# Debug_Breakout.net
KiCad netlist of a schematic drawn in EAGLE
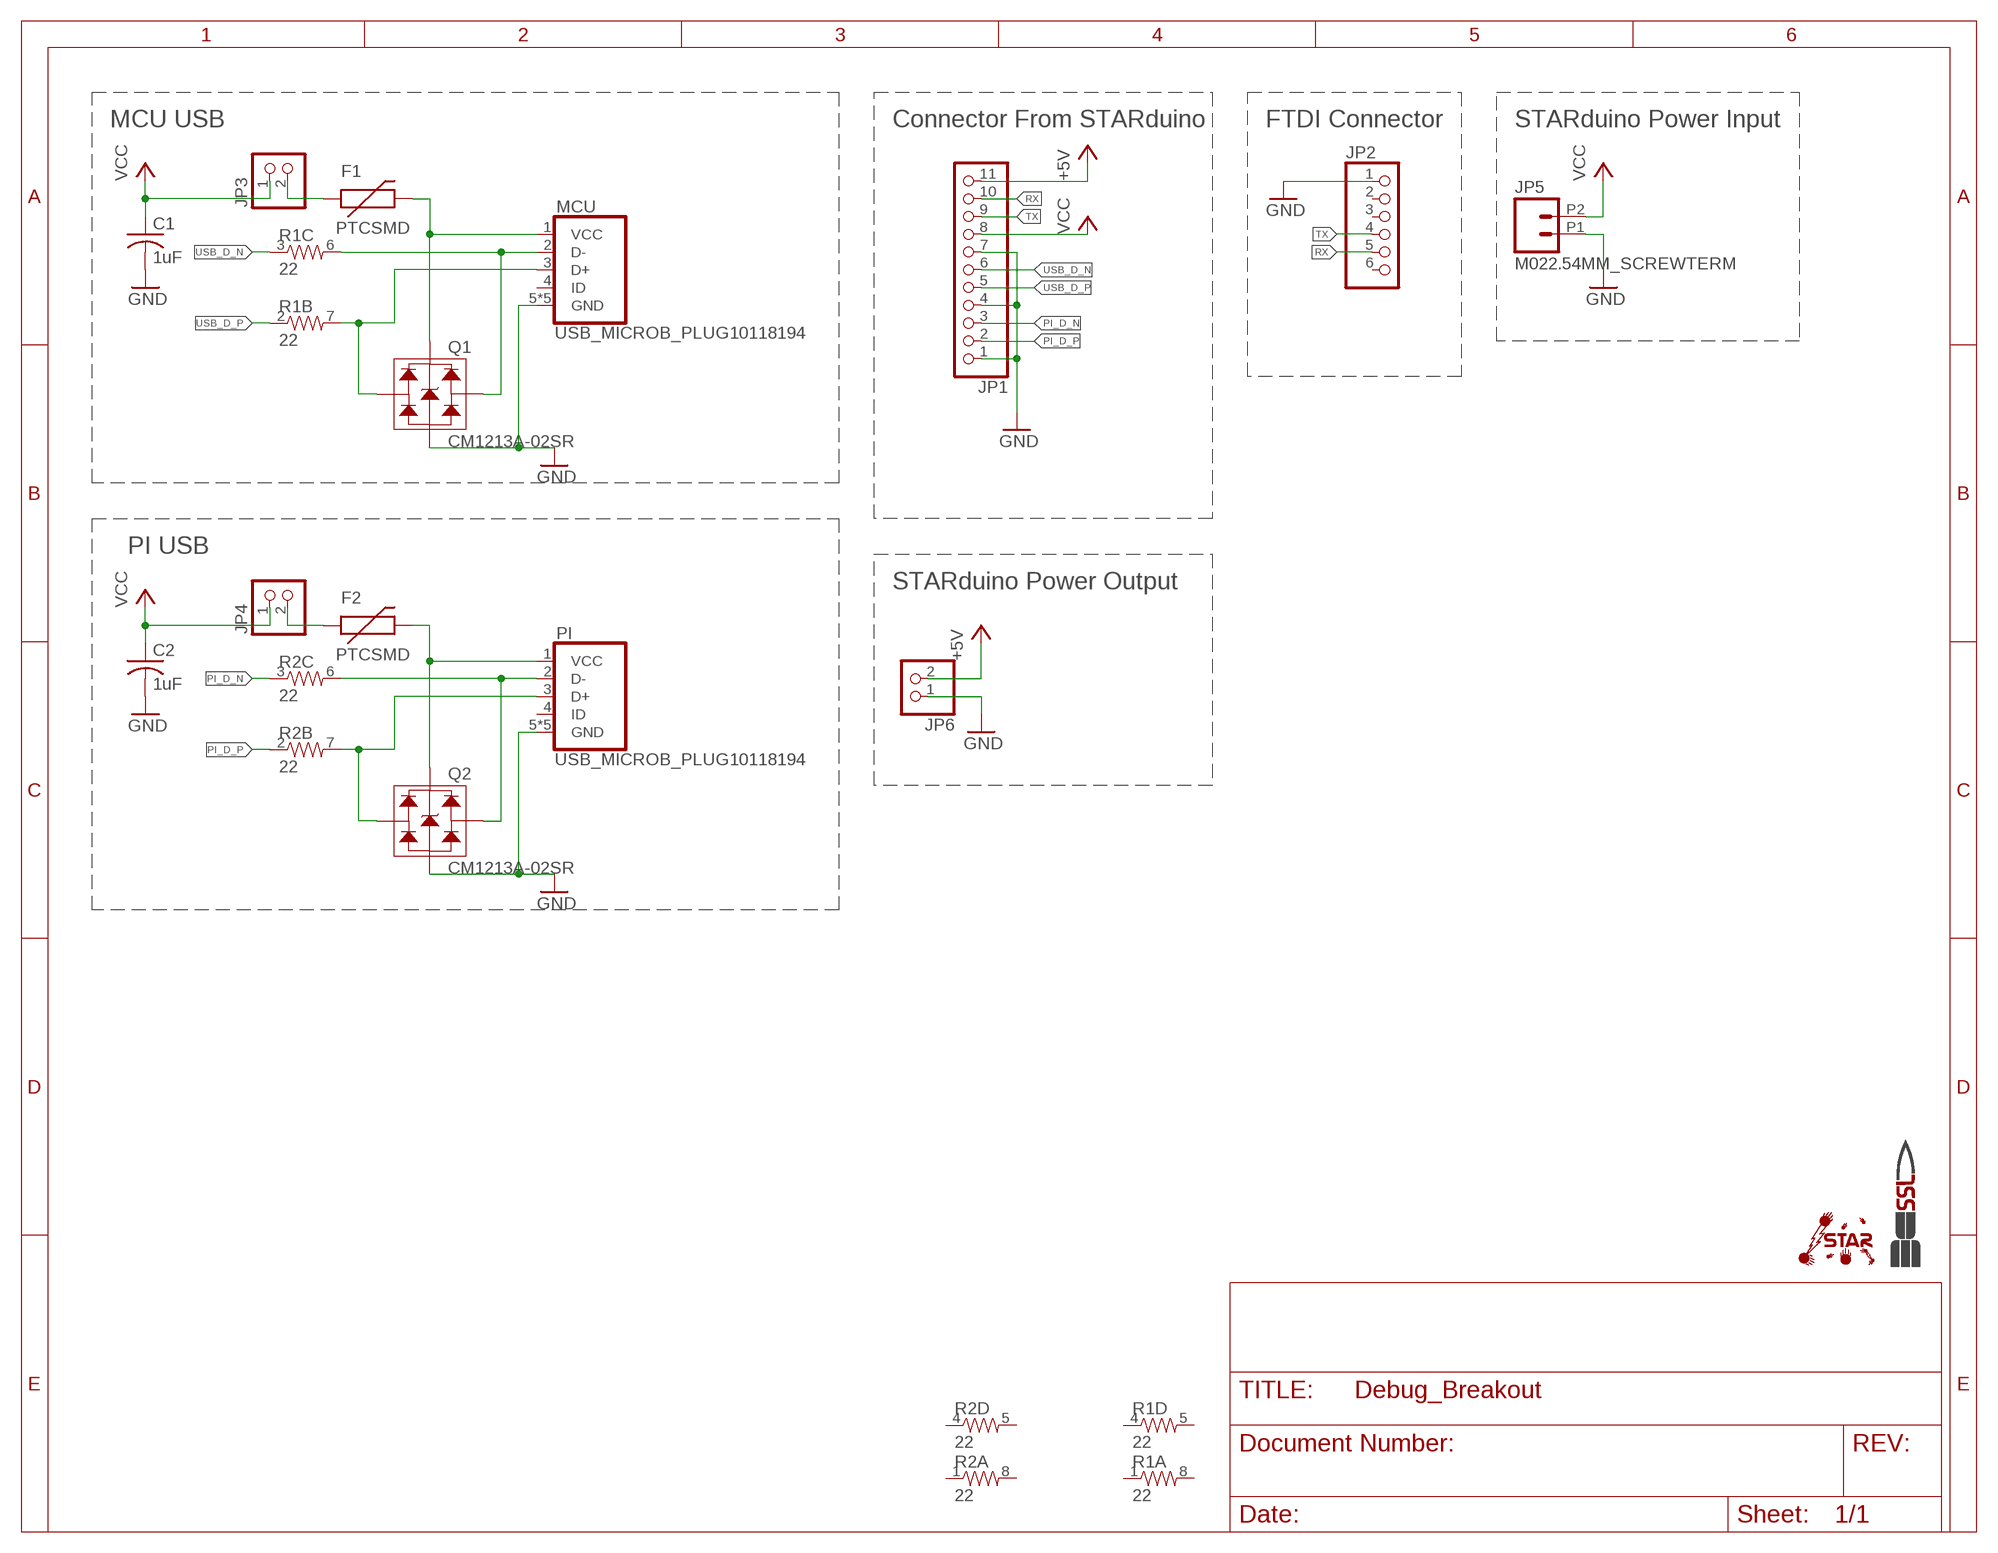
[diagram p0: schematic, sheet 1]

(export (version "E")
  (design (tool "Eeschema 10.0.6"))
  (components
    (comp (ref "C1")
      (value "1uF")
      (footprint "eagle-import:C0603")
      (libsource (lib "eagle-import") (part "C-USC0603"))
    )
    (comp (ref "C2")
      (value "1uF")
      (footprint "eagle-import:C0603")
      (libsource (lib "eagle-import") (part "C-USC0603"))
    )
    (comp (ref "F1")
      (value "PTCSMD")
      (footprint "eagle-import:PTC-1206")
      (libsource (lib "eagle-import") (part "PTCSMD"))
    )
    (comp (ref "F2")
      (value "PTCSMD")
      (footprint "eagle-import:PTC-1206")
      (libsource (lib "eagle-import") (part "PTCSMD"))
    )
    (comp (ref "JP1")
      (value "PINHD-1X11")
      (footprint "eagle-import:1X11")
      (libsource (lib "eagle-import") (part "PINHD-1X11"))
    )
    (comp (ref "JP2")
      (value "PINHD-1X6")
      (footprint "eagle-import:1X06")
      (libsource (lib "eagle-import") (part "PINHD-1X6"))
    )
    (comp (ref "JP3")
      (value "PINHD-1X2")
      (footprint "eagle-import:1X02")
      (libsource (lib "eagle-import") (part "PINHD-1X2"))
    )
    (comp (ref "JP4")
      (value "PINHD-1X2")
      (footprint "eagle-import:1X02")
      (libsource (lib "eagle-import") (part "PINHD-1X2"))
    )
    (comp (ref "JP5")
      (value "M022.54MM_SCREWTERM")
      (footprint "eagle-import:1X02_2.54_SCREWTERM")
      (libsource (lib "eagle-import") (part "M022.54MM_SCREWTERM"))
    )
    (comp (ref "JP6")
      (value "PINHD-1X2")
      (footprint "eagle-import:1X02")
      (libsource (lib "eagle-import") (part "PINHD-1X2"))
    )
    (comp (ref "MCU")
      (value "USB_MICROB_PLUG10118194")
      (footprint "eagle-import:MICRO-B-10118194")
      (libsource (lib "eagle-import") (part "USB_MICROB_PLUG10118194"))
    )
    (comp (ref "PI")
      (value "USB_MICROB_PLUG10118194")
      (footprint "eagle-import:MICRO-B-10118194")
      (libsource (lib "eagle-import") (part "USB_MICROB_PLUG10118194"))
    )
    (comp (ref "Q1")
      (value "CM1213A-02SR")
      (footprint "eagle-import:SOT143-4")
      (libsource (lib "eagle-import") (part "CM1213A-02SR"))
    )
    (comp (ref "Q2")
      (value "CM1213A-02SR")
      (footprint "eagle-import:SOT143-4")
      (libsource (lib "eagle-import") (part "CM1213A-02SR"))
    )
    (comp (ref "R1")
      (value "22")
      (footprint "eagle-import:0603-ARV")
      (libsource (lib "eagle-import") (part "RESISTOR-ARRAY0603-ARV"))
    )
    (comp (ref "R2")
      (value "22")
      (footprint "eagle-import:0603-ARV")
      (libsource (lib "eagle-import") (part "RESISTOR-ARRAY0603-ARV"))
    )
    (comp (ref "U$1")
      (value "SSL.3IN_SILK")
      (footprint "eagle-import:SSL_SILK_.3IN")
      (libsource (lib "eagle-import") (part "SSL.3IN_SILK"))
    )
    (comp (ref "U$2")
      (value "STAR")
      (footprint "eagle-import:STAR_.3IN")
      (libsource (lib "eagle-import") (part "STAR"))
    )
  )
  (nets
    (net (code "1") (name "+5V") (class "Default")
      (node (ref "JP1") (pin "11") (pinfunction "11_11") (pintype "passive"))
      (node (ref "JP6") (pin "2") (pinfunction "2_2") (pintype "passive"))
    )
    (net (code "2") (name "GND") (class "Default")
      (node (ref "C1") (pin "2") (pinfunction "2_2") (pintype "passive"))
      (node (ref "C2") (pin "2") (pinfunction "2_2") (pintype "passive"))
      (node (ref "JP1") (pin "1") (pinfunction "1_1") (pintype "passive"))
      (node (ref "JP1") (pin "4") (pinfunction "4_4") (pintype "passive"))
      (node (ref "JP1") (pin "7") (pinfunction "7_7") (pintype "passive"))
      (node (ref "JP2") (pin "1") (pinfunction "1_1") (pintype "passive"))
      (node (ref "JP5") (pin "P1") (pinfunction "1_P1") (pintype "passive"))
      (node (ref "JP6") (pin "1") (pinfunction "1_1") (pintype "passive"))
      (node (ref "MCU") (pin "5") (pinfunction "GND_5") (pintype "bidirectional"))
      (node (ref "MCU") (pin "S1") (pinfunction "GND_S1") (pintype "bidirectional"))
      (node (ref "MCU") (pin "S2") (pinfunction "GND_S2") (pintype "bidirectional"))
      (node (ref "MCU") (pin "S3") (pinfunction "GND_S3") (pintype "bidirectional"))
      (node (ref "MCU") (pin "S4") (pinfunction "GND_S4") (pintype "bidirectional"))
      (node (ref "PI") (pin "5") (pinfunction "GND_5") (pintype "bidirectional"))
      (node (ref "PI") (pin "S1") (pinfunction "GND_S1") (pintype "bidirectional"))
      (node (ref "PI") (pin "S2") (pinfunction "GND_S2") (pintype "bidirectional"))
      (node (ref "PI") (pin "S3") (pinfunction "GND_S3") (pintype "bidirectional"))
      (node (ref "PI") (pin "S4") (pinfunction "GND_S4") (pintype "bidirectional"))
      (node (ref "Q1") (pin "P$1") (pinfunction "GND_P$1") (pintype "bidirectional"))
      (node (ref "Q2") (pin "P$1") (pinfunction "GND_P$1") (pintype "bidirectional"))
    )
    (net (code "3") (name "Net-(F1-Pad1)") (class "Default")
      (node (ref "F1") (pin "1") (pinfunction "1_1") (pintype "bidirectional"))
      (node (ref "JP3") (pin "2") (pinfunction "2_2") (pintype "passive"))
    )
    (net (code "4") (name "Net-(F2-Pad1)") (class "Default")
      (node (ref "F2") (pin "1") (pinfunction "1_1") (pintype "bidirectional"))
      (node (ref "JP4") (pin "2") (pinfunction "2_2") (pintype "passive"))
    )
    (net (code "5") (name "Net-(MCU-D+)") (class "Default")
      (node (ref "MCU") (pin "3") (pinfunction "D+_3") (pintype "bidirectional"))
      (node (ref "Q1") (pin "P$2") (pinfunction "CH1_P$2") (pintype "bidirectional"))
      (node (ref "R1") (pin "7") (pinfunction "2_7") (pintype "passive"))
    )
    (net (code "6") (name "Net-(MCU-D-)") (class "Default")
      (node (ref "MCU") (pin "2") (pinfunction "D-_2") (pintype "bidirectional"))
      (node (ref "Q1") (pin "P$3") (pinfunction "CH2_P$3") (pintype "bidirectional"))
      (node (ref "R1") (pin "6") (pinfunction "2_6") (pintype "passive"))
    )
    (net (code "7") (name "Net-(MCU-VCC)") (class "Default")
      (node (ref "F1") (pin "2") (pinfunction "2_2") (pintype "bidirectional"))
      (node (ref "MCU") (pin "1") (pinfunction "VCC_1") (pintype "bidirectional"))
      (node (ref "Q1") (pin "P$4") (pinfunction "VCC_P$4") (pintype "bidirectional"))
    )
    (net (code "8") (name "Net-(PI-D+)") (class "Default")
      (node (ref "PI") (pin "3") (pinfunction "D+_3") (pintype "bidirectional"))
      (node (ref "Q2") (pin "P$2") (pinfunction "CH1_P$2") (pintype "bidirectional"))
      (node (ref "R2") (pin "7") (pinfunction "2_7") (pintype "passive"))
    )
    (net (code "9") (name "Net-(PI-D-)") (class "Default")
      (node (ref "PI") (pin "2") (pinfunction "D-_2") (pintype "bidirectional"))
      (node (ref "Q2") (pin "P$3") (pinfunction "CH2_P$3") (pintype "bidirectional"))
      (node (ref "R2") (pin "6") (pinfunction "2_6") (pintype "passive"))
    )
    (net (code "10") (name "Net-(PI-VCC)") (class "Default")
      (node (ref "F2") (pin "2") (pinfunction "2_2") (pintype "bidirectional"))
      (node (ref "PI") (pin "1") (pinfunction "VCC_1") (pintype "bidirectional"))
      (node (ref "Q2") (pin "P$4") (pinfunction "VCC_P$4") (pintype "bidirectional"))
    )
    (net (code "11") (name "PI_D_N") (class "Default")
      (node (ref "JP1") (pin "3") (pinfunction "3_3") (pintype "passive"))
      (node (ref "R2") (pin "3") (pinfunction "1_3") (pintype "passive"))
    )
    (net (code "12") (name "PI_D_P") (class "Default")
      (node (ref "JP1") (pin "2") (pinfunction "2_2") (pintype "passive"))
      (node (ref "R2") (pin "2") (pinfunction "1_2") (pintype "passive"))
    )
    (net (code "13") (name "RX") (class "Default")
      (node (ref "JP1") (pin "10") (pinfunction "10_10") (pintype "passive"))
      (node (ref "JP2") (pin "5") (pinfunction "5_5") (pintype "passive"))
    )
    (net (code "14") (name "TX") (class "Default")
      (node (ref "JP1") (pin "9") (pinfunction "9_9") (pintype "passive"))
      (node (ref "JP2") (pin "4") (pinfunction "4_4") (pintype "passive"))
    )
    (net (code "15") (name "USB_D_N") (class "Default")
      (node (ref "JP1") (pin "6") (pinfunction "6_6") (pintype "passive"))
      (node (ref "R1") (pin "3") (pinfunction "1_3") (pintype "passive"))
    )
    (net (code "16") (name "USB_D_P") (class "Default")
      (node (ref "JP1") (pin "5") (pinfunction "5_5") (pintype "passive"))
      (node (ref "R1") (pin "2") (pinfunction "1_2") (pintype "passive"))
    )
    (net (code "17") (name "VCC") (class "Default")
      (node (ref "C1") (pin "1") (pinfunction "1_1") (pintype "passive"))
      (node (ref "C2") (pin "1") (pinfunction "1_1") (pintype "passive"))
      (node (ref "JP1") (pin "8") (pinfunction "8_8") (pintype "passive"))
      (node (ref "JP3") (pin "1") (pinfunction "1_1") (pintype "passive"))
      (node (ref "JP4") (pin "1") (pinfunction "1_1") (pintype "passive"))
      (node (ref "JP5") (pin "P2") (pinfunction "2_P2") (pintype "passive"))
    )
    (net (code "18") (name "unconnected-(JP2-Pad2)") (class "Default")
      (node (ref "JP2") (pin "2") (pinfunction "2_2") (pintype "passive"))
    )
    (net (code "19") (name "unconnected-(JP2-Pad3)") (class "Default")
      (node (ref "JP2") (pin "3") (pinfunction "3_3") (pintype "passive"))
    )
    (net (code "20") (name "unconnected-(JP2-Pad6)") (class "Default")
      (node (ref "JP2") (pin "6") (pinfunction "6_6") (pintype "passive"))
    )
    (net (code "21") (name "unconnected-(MCU-ID-Pad4)") (class "Default")
      (node (ref "MCU") (pin "4") (pinfunction "ID_4") (pintype "bidirectional"))
    )
    (net (code "22") (name "unconnected-(PI-ID-Pad4)") (class "Default")
      (node (ref "PI") (pin "4") (pinfunction "ID_4") (pintype "bidirectional"))
    )
    (net (code "23") (name "unconnected-(R1-Pad1)") (class "Default")
      (node (ref "R1") (pin "1") (pinfunction "1_1") (pintype "passive"))
    )
    (net (code "24") (name "unconnected-(R1A-2-Pad8)") (class "Default")
      (node (ref "R1") (pin "8") (pinfunction "2_8") (pintype "passive"))
    )
    (net (code "25") (name "unconnected-(R1D-1-Pad4)") (class "Default")
      (node (ref "R1") (pin "4") (pinfunction "1_4") (pintype "passive"))
    )
    (net (code "26") (name "unconnected-(R1D-2-Pad5)") (class "Default")
      (node (ref "R1") (pin "5") (pinfunction "2_5") (pintype "passive"))
    )
    (net (code "27") (name "unconnected-(R2-Pad1)") (class "Default")
      (node (ref "R2") (pin "1") (pinfunction "1_1") (pintype "passive"))
    )
    (net (code "28") (name "unconnected-(R2A-2-Pad8)") (class "Default")
      (node (ref "R2") (pin "8") (pinfunction "2_8") (pintype "passive"))
    )
    (net (code "29") (name "unconnected-(R2D-1-Pad4)") (class "Default")
      (node (ref "R2") (pin "4") (pinfunction "1_4") (pintype "passive"))
    )
    (net (code "30") (name "unconnected-(R2D-2-Pad5)") (class "Default")
      (node (ref "R2") (pin "5") (pinfunction "2_5") (pintype "passive"))
    )
  )
)
